# 05-Power.net
KiCad netlist of a schematic drawn in Altium Designer
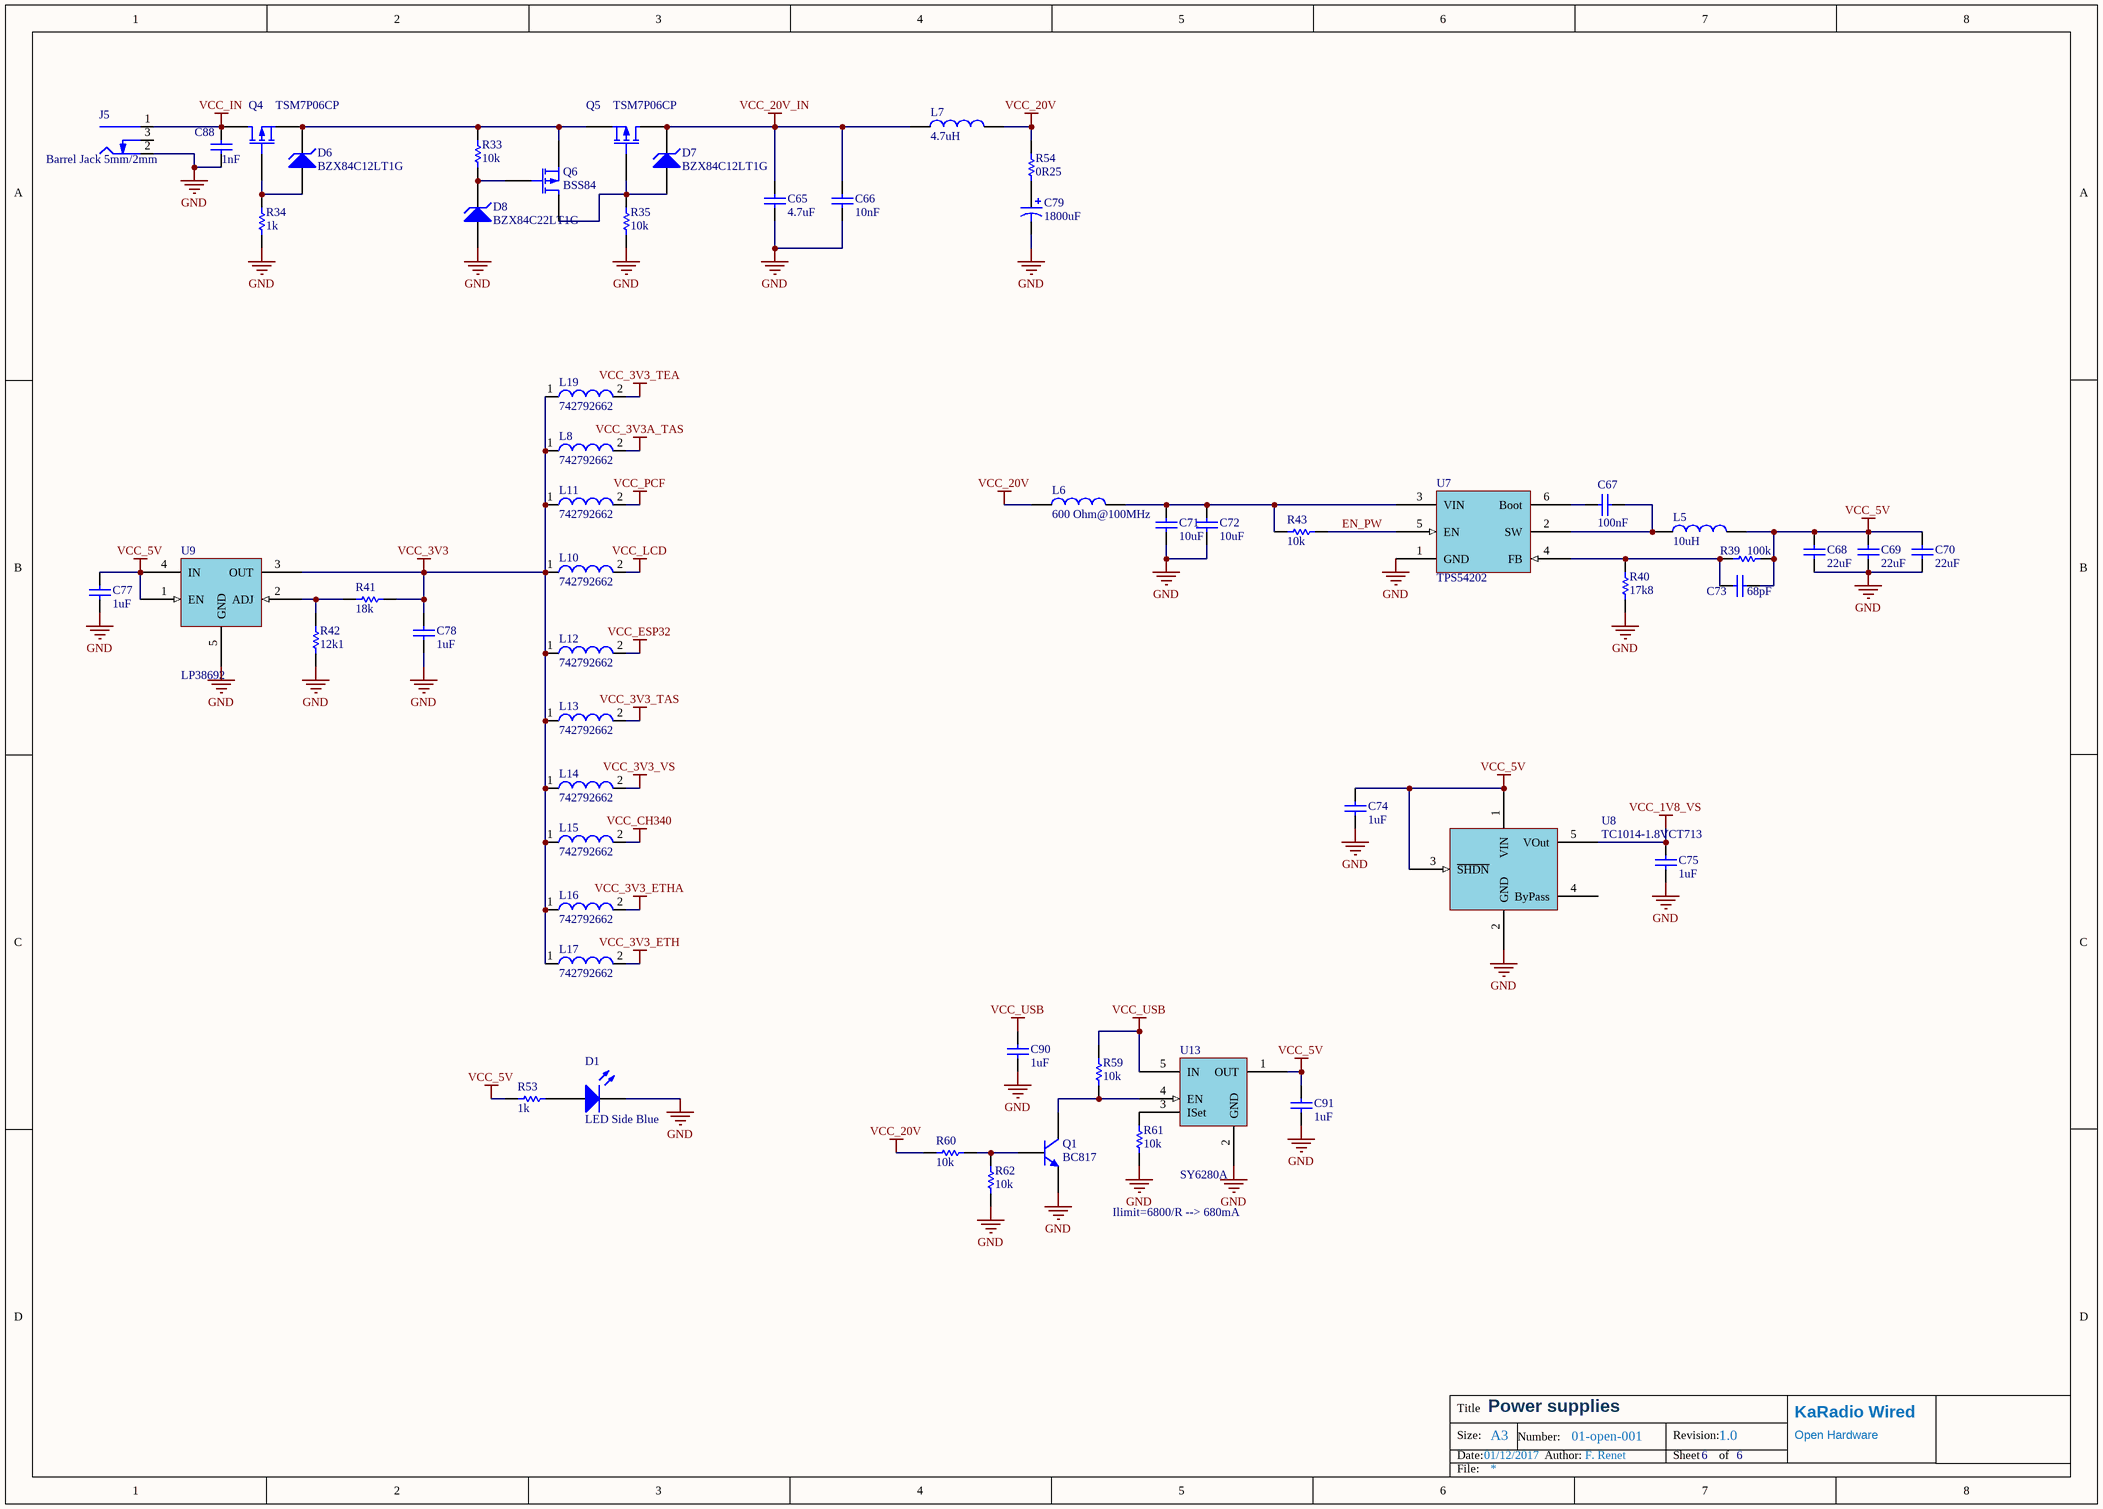
[diagram p0: 05-Power.SchDoc]

(export (version "E")
  (design (tool "Eeschema 10.0.6"))
  (components
    (comp (ref "C65")
      (value "4.7uF")
      (footprint "Aptustech:CAPC3216X16N")
      (description "4.7uF 50V 1206 X5R")
      (fields (field (name "VOLTAGE") "50V") (field (name "TOLERANCE") "10%"))
      (libsource (lib "Cap_1206") (part "4.7uF 50V 1206 X5R"))
    )
    (comp (ref "C66")
      (value "10nF")
      (footprint "Aptustech:CAPC1608X06N")
      (description "10nF 50V 0603 NP0")
      (fields (field (name "VOLTAGE") "50V") (field (name "TOLERANCE") "10%"))
      (libsource (lib "Cap_0603") (part "10nF 50V 0603 NP0"))
    )
    (comp (ref "C67")
      (value "100nF")
      (footprint "Aptustech:CAPC2012X14N")
      (description "100nF 50V 0805 X5R")
      (fields (field (name "VOLTAGE") "50V") (field (name "TOLERANCE") "10%"))
      (libsource (lib "Cap_0805") (part "100nF 50V 0805 X5R_1"))
    )
    (comp (ref "C68")
      (value "22uF")
      (footprint "Aptustech:CAPC2012X14N")
      (description "22uF 10V 0805 X5R")
      (fields (field (name "VOLTAGE") "10V") (field (name "TOLERANCE") "10%"))
      (libsource (lib "Cap_0805") (part "22uF 10V 0805 X5R"))
    )
    (comp (ref "C69")
      (value "22uF")
      (footprint "Aptustech:CAPC2012X14N")
      (description "22uF 10V 0805 X5R")
      (fields (field (name "VOLTAGE") "10V") (field (name "TOLERANCE") "10%"))
      (libsource (lib "Cap_0805") (part "22uF 10V 0805 X5R"))
    )
    (comp (ref "C70")
      (value "22uF")
      (footprint "Aptustech:CAPC2012X14N")
      (description "22uF 10V 0805 X5R")
      (fields (field (name "VOLTAGE") "10V") (field (name "TOLERANCE") "10%"))
      (libsource (lib "Cap_0805") (part "22uF 10V 0805 X5R"))
    )
    (comp (ref "C71")
      (value "10uF")
      (footprint "Aptustech:CAPC3216X16N")
      (description "10uF 50V 1206 X5R")
      (fields (field (name "VOLTAGE") "50V") (field (name "TOLERANCE") "10%"))
      (libsource (lib "Cap_1206") (part "10uF 50V 1206 X5R"))
    )
    (comp (ref "C72")
      (value "10uF")
      (footprint "Aptustech:CAPC3216X16N")
      (description "10uF 50V 1206 X5R")
      (fields (field (name "VOLTAGE") "50V") (field (name "TOLERANCE") "10%"))
      (libsource (lib "Cap_1206") (part "10uF 50V 1206 X5R"))
    )
    (comp (ref "C73")
      (value "68pF")
      (footprint "Aptustech:CAPC1608X06N")
      (description "68pF 50V 0603 NP0")
      (fields (field (name "VOLTAGE") "50V") (field (name "TOLERANCE") "10%"))
      (libsource (lib "Cap_0603") (part "68pF 50V 0603 NP0"))
    )
    (comp (ref "C74")
      (value "1uF")
      (footprint "Aptustech:CAPC1608X06N")
      (description "1uF 16V 0603 X7R")
      (fields (field (name "VOLTAGE") "16V") (field (name "TOLERANCE") "10%"))
      (libsource (lib "Cap_0603") (part "1uF 16V 0603 X7R"))
    )
    (comp (ref "C75")
      (value "1uF")
      (footprint "Aptustech:CAPC1608X06N")
      (description "1uF 16V 0603 X7R")
      (fields (field (name "VOLTAGE") "16V") (field (name "TOLERANCE") "10%"))
      (libsource (lib "Cap_0603") (part "1uF 16V 0603 X7R"))
    )
    (comp (ref "C77")
      (value "1uF")
      (footprint "Aptustech:CAPC1608X06N")
      (description "1uF 16V 0603 X7R")
      (fields (field (name "VOLTAGE") "16V") (field (name "TOLERANCE") "10%"))
      (libsource (lib "Cap_0603") (part "1uF 16V 0603 X7R"))
    )
    (comp (ref "C78")
      (value "1uF")
      (footprint "Aptustech:CAPC1608X06N")
      (description "1uF 16V 0603 X7R")
      (fields (field (name "VOLTAGE") "16V") (field (name "TOLERANCE") "10%"))
      (libsource (lib "Cap_0603") (part "1uF 16V 0603 X7R"))
    )
    (comp (ref "C79")
      (value "1800uF")
      (footprint "Aptustech:Cap_POL_12.5mm_20mm_TH")
      (description "Aluminum Capacitor 1800uF 25V TH 12.5mm 20mm")
      (fields (field (name "VOLTAGE") "25V") (field (name "TOLERANCE") "20%"))
      (libsource (lib "Cap_Aluminum") (part "1800uF 25V 12.5mm 20mm"))
    )
    (comp (ref "C88")
      (value "1nF")
      (footprint "Aptustech:CAPC3216X16N")
      (description "1nF 100V 1206 X7R")
      (fields (field (name "VOLTAGE") "100V") (field (name "TOLERANCE") "10%"))
      (libsource (lib "Cap_1206") (part "1nF 100V 1206 X7R"))
    )
    (comp (ref "C90")
      (value "1uF")
      (footprint "Aptustech:CAPC1608X06N")
      (description "1uF 16V 0603 X7R")
      (fields (field (name "VOLTAGE") "16V") (field (name "TOLERANCE") "10%"))
      (libsource (lib "Cap_0603") (part "1uF 16V 0603 X7R"))
    )
    (comp (ref "C91")
      (value "1uF")
      (footprint "Aptustech:CAPC1608X06N")
      (description "1uF 16V 0603 X7R")
      (fields (field (name "VOLTAGE") "16V") (field (name "TOLERANCE") "10%"))
      (libsource (lib "Cap_0603") (part "1uF 16V 0603 X7R"))
    )
    (comp (ref "D1")
      (value "LED Side Blue")
      (footprint "Aptustech:APA1606")
      (description "Side Emitting LED Blue")
      (fields (field (name "MANUFACTURER") "Kingbtigth") (field (name "PARTNUMBER") "APA1606QBC/D"))
      (libsource (lib "Diodes") (part "LED Side Blue"))
    )
    (comp (ref "D6")
      (value "BZX84C12LT1G")
      (footprint "Aptustech:SOT95P230X110-3N")
      (description "DIODE ZENER 12V 250MW SOT23-3")
      (fields (field (name "MANUFACTURER") "ON Semi"))
      (libsource (lib "Diodes") (part "BZX84C12LT1G"))
    )
    (comp (ref "D7")
      (value "BZX84C12LT1G")
      (footprint "Aptustech:SOT95P230X110-3N")
      (description "DIODE ZENER 12V 250MW SOT23-3")
      (fields (field (name "MANUFACTURER") "ON Semi"))
      (libsource (lib "Diodes") (part "BZX84C12LT1G"))
    )
    (comp (ref "D8")
      (value "BZX84C22LT1G")
      (footprint "Aptustech:SOT95P230X110-3N")
      (description "DIODE ZENER 22V 250MW SOT23-3")
      (fields (field (name "MANUFACTURER") "ON Semi"))
      (libsource (lib "Diodes") (part "BZX84C22LT1G"))
    )
    (comp (ref "J5")
      (value "Barrel Jack 5mm/2mm")
      (footprint "Aptustech:CUI PJ-102AH")
      (description "CONN PWR JACK 2X5.5MM SOLDER")
      (fields (field (name "PARTNUMBER") "PJ-102AH") (field (name "MANUFACTURER") "CUI"))
      (libsource (lib "Connectors") (part "Barrel Connector"))
    )
    (comp (ref "L5")
      (value "10uH")
      (footprint "Aptustech:SRN6045")
      (description "SRN6045-100M 10uH 2.5A 6x6x4,5mm")
      (fields (field (name "PARTNUMBER") "SRN6045-100M") (field (name "MANUFACTURER") "Bourns"))
      (libsource (lib "Inductor") (part "SRN6045-100M"))
    )
    (comp (ref "L6")
      (value "600 Ohm@100MHz")
      (footprint "Aptustech:IND2012X14N")
      (description "0805, 600 Ohm@100MHz, 2.1A")
      (fields (field (name "PARTNUMBER") "74279220601") (field (name "MANUFACTURER") "Wurth"))
      (libsource (lib "Inductor") (part "74279220601"))
    )
    (comp (ref "L7")
      (value "4.7uH")
      (footprint "Aptustech:1255AY")
      (description "1255AY-4R7M=P3 4.7uH 4A")
      (fields (field (name "PARTNUMBER") "1255AY-4R7M=P3") (field (name "MANUFACTURER") "Murata"))
      (libsource (lib "Inductor") (part "1255AY-4R7M=P3"))
    )
    (comp (ref "L8")
      (value "742792662")
      (footprint "PcbLib:CAPC0603(1608)")
      (description "SMD EMI Suppression Ferrite Bead WE-CBF, Z = 1000 Ohm")
      (fields (field (name "MANUFACTURER") "Wurth"))
      (libsource (lib "Altium Content Vault") (part "CMP-0220-00178-1"))
    )
    (comp (ref "L10")
      (value "742792662")
      (footprint "PcbLib:CAPC0603(1608)")
      (description "SMD EMI Suppression Ferrite Bead WE-CBF, Z = 1000 Ohm")
      (fields (field (name "MANUFACTURER") "Wurth"))
      (libsource (lib "Altium Content Vault") (part "CMP-0220-00178-1"))
    )
    (comp (ref "L11")
      (value "742792662")
      (footprint "PcbLib:CAPC0603(1608)")
      (description "SMD EMI Suppression Ferrite Bead WE-CBF, Z = 1000 Ohm")
      (fields (field (name "MANUFACTURER") "Wurth"))
      (libsource (lib "Altium Content Vault") (part "CMP-0220-00178-1"))
    )
    (comp (ref "L12")
      (value "742792662")
      (footprint "PcbLib:CAPC0603(1608)")
      (description "SMD EMI Suppression Ferrite Bead WE-CBF, Z = 1000 Ohm")
      (fields (field (name "MANUFACTURER") "Wurth"))
      (libsource (lib "Altium Content Vault") (part "CMP-0220-00178-1"))
    )
    (comp (ref "L13")
      (value "742792662")
      (footprint "PcbLib:CAPC0603(1608)")
      (description "SMD EMI Suppression Ferrite Bead WE-CBF, Z = 1000 Ohm")
      (fields (field (name "MANUFACTURER") "Wurth"))
      (libsource (lib "Altium Content Vault") (part "CMP-0220-00178-1"))
    )
    (comp (ref "L14")
      (value "742792662")
      (footprint "PcbLib:CAPC0603(1608)")
      (description "SMD EMI Suppression Ferrite Bead WE-CBF, Z = 1000 Ohm")
      (fields (field (name "MANUFACTURER") "Wurth"))
      (libsource (lib "Altium Content Vault") (part "CMP-0220-00178-1"))
    )
    (comp (ref "L15")
      (value "742792662")
      (footprint "PcbLib:CAPC0603(1608)")
      (description "SMD EMI Suppression Ferrite Bead WE-CBF, Z = 1000 Ohm")
      (fields (field (name "MANUFACTURER") "Wurth"))
      (libsource (lib "Altium Content Vault") (part "CMP-0220-00178-1"))
    )
    (comp (ref "L16")
      (value "742792662")
      (footprint "PcbLib:CAPC0603(1608)")
      (description "SMD EMI Suppression Ferrite Bead WE-CBF, Z = 1000 Ohm")
      (fields (field (name "MANUFACTURER") "Wurth"))
      (libsource (lib "Altium Content Vault") (part "CMP-0220-00178-1"))
    )
    (comp (ref "L17")
      (value "742792662")
      (footprint "PcbLib:CAPC0603(1608)")
      (description "SMD EMI Suppression Ferrite Bead WE-CBF, Z = 1000 Ohm")
      (fields (field (name "MANUFACTURER") "Wurth"))
      (libsource (lib "Altium Content Vault") (part "CMP-0220-00178-1"))
    )
    (comp (ref "L19")
      (value "742792662")
      (footprint "CAPC0603(1608)")
      (description "SMD EMI Suppression Ferrite Bead WE-CBF, Z = 1000 Ohm")
      (fields (field (name "MANUFACTURER") "Wurth"))
      (libsource (lib "altium-import") (part "root_0_CMP-0220-00178-1_"))
    )
    (comp (ref "Q1")
      (value "BC817")
      (footprint "Aptustech:SOT95P230X110-3N")
      (description "BC817 NPN  45V SOT23")
      (fields (field (name "PARTNUMBER") "BC817-40,215") (field (name "MANUFACTURER") "Nexperia"))
      (libsource (lib "Transistor_Switch") (part "BC817_SOT23"))
    )
    (comp (ref "Q4")
      (value "TSM7P06CP")
      (footprint "Aptustech:TO252")
      (description "MOSFET P-CHANNEL 60V 7A TO252")
      (fields (field (name "MANUFACTURER") "Taiwan Semiconductor Corp"))
      (libsource (lib "Transistor_Switch") (part "TSM7P06CP"))
    )
    (comp (ref "Q5")
      (value "TSM7P06CP")
      (footprint "Aptustech:TO252")
      (description "MOSFET P-CHANNEL 60V 7A TO252")
      (fields (field (name "MANUFACTURER") "Taiwan Semiconductor Corp"))
      (libsource (lib "Transistor_Switch") (part "TSM7P06CP"))
    )
    (comp (ref "Q6")
      (value "BSS84")
      (footprint "Aptustech:SOT95P230X110-3N")
      (description "MOSFET P-CH 60V 170MA SOT-23")
      (fields (field (name "PARTNUMBER") "BSS84PH6433XTMA1") (field (name "MANUFACTURER") "Infineon"))
      (libsource (lib "Transistor_Switch") (part "BSS84"))
    )
    (comp (ref "R33")
      (value "10k")
      (footprint "Aptustech:RESC1608X06N")
      (description "Resistor 10k 0603 1%")
      (fields (field (name "TOLERANCE") "1%") (field (name "Comment") "10k_0603"))
      (libsource (lib "Res_0603") (part "10k"))
    )
    (comp (ref "R34")
      (value "1k")
      (footprint "Aptustech:RESC1608X06N")
      (description "Resistor 1k 0603 1%")
      (fields (field (name "TOLERANCE") "1%") (field (name "Comment") "1k_0603"))
      (libsource (lib "Res_0603") (part "1k"))
    )
    (comp (ref "R35")
      (value "10k")
      (footprint "Aptustech:RESC1608X06N")
      (description "Resistor 10k 0603 1%")
      (fields (field (name "TOLERANCE") "1%") (field (name "Comment") "10k_0603"))
      (libsource (lib "Res_0603") (part "10k"))
    )
    (comp (ref "R39")
      (value "100k")
      (footprint "Aptustech:RESC1608X06N")
      (description "Resistor 100k 0603 1%")
      (fields (field (name "TOLERANCE") "1%") (field (name "Comment") "100k_0603"))
      (libsource (lib "Res_0603") (part "100k"))
    )
    (comp (ref "R40")
      (value "17k8")
      (footprint "Aptustech:RESC1608X06N")
      (description "Resistor 17k8 0603 1%")
      (fields (field (name "TOLERANCE") "1%") (field (name "Comment") "17k8_0603"))
      (libsource (lib "Res_0603") (part "17k8"))
    )
    (comp (ref "R41")
      (value "18k")
      (footprint "Aptustech:RESC1608X06N")
      (description "Resistor 18k 0603 1%")
      (fields (field (name "TOLERANCE") "1%") (field (name "Comment") "18k_0603"))
      (libsource (lib "Res_0603") (part "18k"))
    )
    (comp (ref "R42")
      (value "12k1")
      (footprint "Aptustech:RESC1608X06N")
      (description "Resistor 12k1 0603 1%")
      (fields (field (name "TOLERANCE") "1%") (field (name "Comment") "12k1_0603"))
      (libsource (lib "Res_0603") (part "12k1"))
    )
    (comp (ref "R43")
      (value "10k")
      (footprint "Aptustech:RESC1608X06N")
      (description "Resistor 10k 0603 1%")
      (fields (field (name "TOLERANCE") "1%") (field (name "Comment") "10k_0603"))
      (libsource (lib "Res_0603") (part "10k"))
    )
    (comp (ref "R53")
      (value "1k")
      (footprint "Aptustech:RESC1608X06N")
      (description "Resistor 1k 0603 1%")
      (fields (field (name "TOLERANCE") "1%") (field (name "Comment") "1k_0603"))
      (libsource (lib "Res_0603") (part "1k"))
    )
    (comp (ref "R54")
      (value "0R25")
      (footprint "Aptustech:RESC3116X07N")
      (description "Resistor 0.25R 1206 1%")
      (fields (field (name "TOLERANCE") "1%") (field (name "Comment") "0R25_1206"))
      (libsource (lib "Res_1206") (part "0R25_1206"))
    )
    (comp (ref "R59")
      (value "10k")
      (footprint "Aptustech:RESC1608X06N")
      (description "Resistor 10k 0603 1%")
      (fields (field (name "TOLERANCE") "1%") (field (name "Comment") "10k_0603"))
      (libsource (lib "Res_0603") (part "10k"))
    )
    (comp (ref "R60")
      (value "10k")
      (footprint "Aptustech:RESC1608X06N")
      (description "Resistor 10k 0603 1%")
      (fields (field (name "TOLERANCE") "1%") (field (name "Comment") "10k_0603"))
      (libsource (lib "Res_0603") (part "10k"))
    )
    (comp (ref "R61")
      (value "10k")
      (footprint "Aptustech:RESC1608X06N")
      (description "Resistor 10k 0603 1%")
      (fields (field (name "TOLERANCE") "1%") (field (name "Comment") "10k_0603"))
      (libsource (lib "Res_0603") (part "10k"))
    )
    (comp (ref "R62")
      (value "10k")
      (footprint "Aptustech:RESC1608X06N")
      (description "Resistor 10k 0603 1%")
      (fields (field (name "TOLERANCE") "1%") (field (name "Comment") "10k_0603"))
      (libsource (lib "Res_0603") (part "10k"))
    )
    (comp (ref "U7")
      (value "TPS54202")
      (footprint "Aptustech:SOT95P245X110-6N")
      (description "4.5V to 28V Input, 2A Output Sync Buck")
      (fields (field (name "PARTNUMBER") "TPS54202DDC") (field (name "MANUFACTURER") "TI"))
      (libsource (lib "LDO_DC-DC") (part "TPS54202"))
    )
    (comp (ref "U8")
      (value "TC1014-1.8VCT713")
      (footprint "Aptustech:SOT95P245X110-5N")
      (description "1.8V LDO 50mA SOT23-5")
      (fields (field (name "MANUFACTURER") "Microchip"))
      (libsource (lib "LDO_DC-DC") (part "TC1014-1.8VCT713"))
    )
    (comp (ref "U9")
      (value "LP38692")
      (footprint "Aptustech:SOT150P700X180-5N")
      (description "REG LIN POS ADJ 1A SOT223-5 LP38692MP-ADJ/NOPB")
      (fields (field (name "PARTNUMBER") "LP38692MP-ADJ/NOPB") (field (name "MANUFACTURER") "TI"))
      (libsource (lib "LDO_DC-DC") (part "LP38692MP-ADJ/NOPB"))
    )
    (comp (ref "U13")
      (value "SY6280A")
      (footprint "Aptustech:SOT95P245X110-5N")
      (description "SOT23-5 USB VCC Switch with current Limit")
      (fields (field (name "MANUFACTURER") "Silergy"))
      (libsource (lib "MISC_IC") (part "SY6280A"))
    )
  )
  (nets
    (net (code "1") (name "/EN_PW") (class "Default")
      (node (ref "R43") (pin "1") (pinfunction "1_1") (pintype "passive"))
      (node (ref "U7") (pin "5") (pinfunction "EN_5") (pintype "input"))
    )
    (net (code "2") (name "GND") (class "Default")
      (node (ref "C65") (pin "1") (pinfunction "1_1") (pintype "passive"))
      (node (ref "C66") (pin "1") (pinfunction "1_1") (pintype "passive"))
      (node (ref "C68") (pin "1") (pinfunction "1_1") (pintype "passive"))
      (node (ref "C69") (pin "1") (pinfunction "1_1") (pintype "passive"))
      (node (ref "C70") (pin "1") (pinfunction "1_1") (pintype "passive"))
      (node (ref "C71") (pin "1") (pinfunction "1_1") (pintype "passive"))
      (node (ref "C72") (pin "1") (pinfunction "1_1") (pintype "passive"))
      (node (ref "C74") (pin "1") (pinfunction "1_1") (pintype "passive"))
      (node (ref "C75") (pin "1") (pinfunction "1_1") (pintype "passive"))
      (node (ref "C77") (pin "1") (pinfunction "1_1") (pintype "passive"))
      (node (ref "C78") (pin "1") (pinfunction "1_1") (pintype "passive"))
      (node (ref "C79") (pin "2") (pinfunction "2_2") (pintype "passive"))
      (node (ref "C88") (pin "1") (pinfunction "1_1") (pintype "passive"))
      (node (ref "C90") (pin "1") (pinfunction "1_1") (pintype "passive"))
      (node (ref "C91") (pin "1") (pinfunction "1_1") (pintype "passive"))
      (node (ref "D1") (pin "1") (pinfunction "K_1") (pintype "passive"))
      (node (ref "D8") (pin "1") (pinfunction "A_1") (pintype "passive"))
      (node (ref "J5") (pin "2") (pinfunction "Outer_2") (pintype "passive"))
      (node (ref "Q1") (pin "2") (pinfunction "E_2") (pintype "passive"))
      (node (ref "R34") (pin "1") (pinfunction "1_1") (pintype "passive"))
      (node (ref "R35") (pin "1") (pinfunction "1_1") (pintype "passive"))
      (node (ref "R40") (pin "1") (pinfunction "1_1") (pintype "passive"))
      (node (ref "R42") (pin "1") (pinfunction "1_1") (pintype "passive"))
      (node (ref "R61") (pin "1") (pinfunction "1_1") (pintype "passive"))
      (node (ref "R62") (pin "2") (pinfunction "2_2") (pintype "passive"))
      (node (ref "U13") (pin "2") (pinfunction "GND_2") (pintype "power_in"))
      (node (ref "U7") (pin "1") (pinfunction "GND_1") (pintype "power_in"))
      (node (ref "U8") (pin "2") (pinfunction "GND_2") (pintype "power_in"))
      (node (ref "U9") (pin "5") (pinfunction "GND_5") (pintype "power_in"))
    )
    (net (code "3") (name "Net-(C79-Pad1)") (class "Default")
      (node (ref "C79") (pin "1") (pinfunction "1_1") (pintype "passive"))
      (node (ref "R54") (pin "1") (pinfunction "1_1") (pintype "passive"))
    )
    (net (code "4") (name "Net-(D1-A)") (class "Default")
      (node (ref "D1") (pin "2") (pinfunction "A_2") (pintype "passive"))
      (node (ref "R53") (pin "1") (pinfunction "1_1") (pintype "passive"))
    )
    (net (code "5") (name "Net-(D6-A)") (class "Default")
      (node (ref "D6") (pin "1") (pinfunction "A_1") (pintype "passive"))
      (node (ref "Q4") (pin "1") (pinfunction "G_1") (pintype "passive"))
      (node (ref "R34") (pin "2") (pinfunction "2_2") (pintype "passive"))
    )
    (net (code "6") (name "Net-(D6-K)") (class "Default")
      (node (ref "D6") (pin "3") (pinfunction "K_3") (pintype "passive"))
      (node (ref "Q4") (pin "3") (pinfunction "S_3") (pintype "passive"))
      (node (ref "Q5") (pin "3") (pinfunction "S_3") (pintype "passive"))
      (node (ref "Q6") (pin "2") (pinfunction "S_2") (pintype "passive"))
      (node (ref "R33") (pin "2") (pinfunction "2_2") (pintype "passive"))
    )
    (net (code "7") (name "Net-(D7-A)") (class "Default")
      (node (ref "D7") (pin "1") (pinfunction "A_1") (pintype "passive"))
      (node (ref "Q5") (pin "1") (pinfunction "G_1") (pintype "passive"))
      (node (ref "Q6") (pin "3") (pinfunction "D_3") (pintype "passive"))
      (node (ref "R35") (pin "2") (pinfunction "2_2") (pintype "passive"))
    )
    (net (code "8") (name "Net-(D8-K)") (class "Default")
      (node (ref "D8") (pin "3") (pinfunction "K_3") (pintype "passive"))
      (node (ref "Q6") (pin "1") (pinfunction "G_1") (pintype "passive"))
      (node (ref "R33") (pin "1") (pinfunction "1_1") (pintype "passive"))
    )
    (net (code "9") (name "Net-(Q1-B)") (class "Default")
      (node (ref "Q1") (pin "1") (pinfunction "B_1") (pintype "passive"))
      (node (ref "R60") (pin "1") (pinfunction "1_1") (pintype "passive"))
      (node (ref "R62") (pin "1") (pinfunction "1_1") (pintype "passive"))
    )
    (net (code "10") (name "Net-(Q1-C)") (class "Default")
      (node (ref "Q1") (pin "3") (pinfunction "C_3") (pintype "passive"))
      (node (ref "R59") (pin "1") (pinfunction "1_1") (pintype "passive"))
      (node (ref "U13") (pin "4") (pinfunction "EN_4") (pintype "input"))
    )
    (net (code "11") (name "Net-(U7-Boot)") (class "Default")
      (node (ref "C67") (pin "1") (pinfunction "1_1") (pintype "passive"))
      (node (ref "U7") (pin "6") (pinfunction "Boot_6") (pintype "passive"))
    )
    (net (code "12") (name "Net-(U7-FB)") (class "Default")
      (node (ref "C73") (pin "1") (pinfunction "1_1") (pintype "passive"))
      (node (ref "R39") (pin "1") (pinfunction "1_1") (pintype "passive"))
      (node (ref "R40") (pin "2") (pinfunction "2_2") (pintype "passive"))
      (node (ref "U7") (pin "4") (pinfunction "FB_4") (pintype "input"))
    )
    (net (code "13") (name "Net-(U7-SW)") (class "Default")
      (node (ref "C67") (pin "2") (pinfunction "2_2") (pintype "passive"))
      (node (ref "L5") (pin "1") (pinfunction "1_1") (pintype "passive"))
      (node (ref "U7") (pin "2") (pinfunction "SW_2") (pintype "power_in"))
    )
    (net (code "14") (name "Net-(U7-VIN)") (class "Default")
      (node (ref "C71") (pin "2") (pinfunction "2_2") (pintype "passive"))
      (node (ref "C72") (pin "2") (pinfunction "2_2") (pintype "passive"))
      (node (ref "L6") (pin "2") (pinfunction "2_2") (pintype "passive"))
      (node (ref "R43") (pin "2") (pinfunction "2_2") (pintype "passive"))
      (node (ref "U7") (pin "3") (pinfunction "VIN_3") (pintype "power_in"))
    )
    (net (code "15") (name "Net-(U9-ADJ)") (class "Default")
      (node (ref "R41") (pin "1") (pinfunction "1_1") (pintype "passive"))
      (node (ref "R42") (pin "2") (pinfunction "2_2") (pintype "passive"))
      (node (ref "U9") (pin "2") (pinfunction "ADJ_2") (pintype "input"))
    )
    (net (code "16") (name "Net-(U13-ISet)") (class "Default")
      (node (ref "R61") (pin "2") (pinfunction "2_2") (pintype "passive"))
      (node (ref "U13") (pin "3") (pinfunction "ISet_3") (pintype "passive"))
    )
    (net (code "17") (name "VCC_1V8_VS") (class "Default")
      (node (ref "C75") (pin "2") (pinfunction "2_2") (pintype "passive"))
      (node (ref "U8") (pin "5") (pinfunction "VOut_5") (pintype "power_in"))
    )
    (net (code "18") (name "VCC_3V3") (class "Default")
      (node (ref "C78") (pin "2") (pinfunction "2_2") (pintype "passive"))
      (node (ref "L10") (pin "1") (pinfunction "1_1") (pintype "passive"))
      (node (ref "L11") (pin "1") (pinfunction "1_1") (pintype "passive"))
      (node (ref "L12") (pin "1") (pinfunction "1_1") (pintype "passive"))
      (node (ref "L13") (pin "1") (pinfunction "1_1") (pintype "passive"))
      (node (ref "L14") (pin "1") (pinfunction "1_1") (pintype "passive"))
      (node (ref "L15") (pin "1") (pinfunction "1_1") (pintype "passive"))
      (node (ref "L16") (pin "1") (pinfunction "1_1") (pintype "passive"))
      (node (ref "L17") (pin "1") (pinfunction "1_1") (pintype "passive"))
      (node (ref "L19") (pin "1") (pinfunction "1_1") (pintype "passive"))
      (node (ref "L8") (pin "1") (pinfunction "1_1") (pintype "passive"))
      (node (ref "R41") (pin "2") (pinfunction "2_2") (pintype "passive"))
      (node (ref "U9") (pin "3") (pinfunction "OUT_3") (pintype "power_in"))
    )
    (net (code "19") (name "VCC_3V3A_TAS") (class "Default")
      (node (ref "L8") (pin "2") (pinfunction "2_2") (pintype "passive"))
    )
    (net (code "20") (name "VCC_3V3_ETH") (class "Default")
      (node (ref "L17") (pin "2") (pinfunction "2_2") (pintype "passive"))
    )
    (net (code "21") (name "VCC_3V3_ETHA") (class "Default")
      (node (ref "L16") (pin "2") (pinfunction "2_2") (pintype "passive"))
    )
    (net (code "22") (name "VCC_3V3_TAS") (class "Default")
      (node (ref "L13") (pin "2") (pinfunction "2_2") (pintype "passive"))
    )
    (net (code "23") (name "VCC_3V3_TEA") (class "Default")
      (node (ref "L19") (pin "2") (pinfunction "2_2") (pintype "passive"))
    )
    (net (code "24") (name "VCC_3V3_VS") (class "Default")
      (node (ref "L14") (pin "2") (pinfunction "2_2") (pintype "passive"))
    )
    (net (code "25") (name "VCC_5V") (class "Default")
      (node (ref "C68") (pin "2") (pinfunction "2_2") (pintype "passive"))
      (node (ref "C69") (pin "2") (pinfunction "2_2") (pintype "passive"))
      (node (ref "C70") (pin "2") (pinfunction "2_2") (pintype "passive"))
      (node (ref "C73") (pin "2") (pinfunction "2_2") (pintype "passive"))
      (node (ref "C74") (pin "2") (pinfunction "2_2") (pintype "passive"))
      (node (ref "C77") (pin "2") (pinfunction "2_2") (pintype "passive"))
      (node (ref "C91") (pin "2") (pinfunction "2_2") (pintype "passive"))
      (node (ref "L5") (pin "2") (pinfunction "2_2") (pintype "passive"))
      (node (ref "R39") (pin "2") (pinfunction "2_2") (pintype "passive"))
      (node (ref "R53") (pin "2") (pinfunction "2_2") (pintype "passive"))
      (node (ref "U13") (pin "1") (pinfunction "OUT_1") (pintype "power_in"))
      (node (ref "U8") (pin "1") (pinfunction "VIN_1") (pintype "power_in"))
      (node (ref "U8") (pin "3") (pinfunction "~{SHDN}_3") (pintype "input"))
      (node (ref "U9") (pin "1") (pinfunction "EN_1") (pintype "input"))
      (node (ref "U9") (pin "4") (pinfunction "IN_4") (pintype "power_in"))
    )
    (net (code "26") (name "VCC_20V") (class "Default")
      (node (ref "L6") (pin "1") (pinfunction "1_1") (pintype "passive"))
      (node (ref "L7") (pin "2") (pinfunction "2_2") (pintype "passive"))
      (node (ref "R54") (pin "2") (pinfunction "2_2") (pintype "passive"))
      (node (ref "R60") (pin "2") (pinfunction "2_2") (pintype "passive"))
    )
    (net (code "27") (name "VCC_20V_IN") (class "Default")
      (node (ref "C65") (pin "2") (pinfunction "2_2") (pintype "passive"))
      (node (ref "C66") (pin "2") (pinfunction "2_2") (pintype "passive"))
      (node (ref "D7") (pin "3") (pinfunction "K_3") (pintype "passive"))
      (node (ref "L7") (pin "1") (pinfunction "1_1") (pintype "passive"))
      (node (ref "Q5") (pin "2") (pinfunction "D_2") (pintype "passive"))
    )
    (net (code "28") (name "VCC_CH340") (class "Default")
      (node (ref "L15") (pin "2") (pinfunction "2_2") (pintype "passive"))
    )
    (net (code "29") (name "VCC_ESP32") (class "Default")
      (node (ref "L12") (pin "2") (pinfunction "2_2") (pintype "passive"))
    )
    (net (code "30") (name "VCC_IN") (class "Default")
      (node (ref "C88") (pin "2") (pinfunction "2_2") (pintype "passive"))
      (node (ref "J5") (pin "1") (pinfunction "Centre_1") (pintype "passive"))
      (node (ref "Q4") (pin "2") (pinfunction "D_2") (pintype "passive"))
    )
    (net (code "31") (name "VCC_LCD") (class "Default")
      (node (ref "L10") (pin "2") (pinfunction "2_2") (pintype "passive"))
    )
    (net (code "32") (name "VCC_PCF") (class "Default")
      (node (ref "L11") (pin "2") (pinfunction "2_2") (pintype "passive"))
    )
    (net (code "33") (name "VCC_USB") (class "Default")
      (node (ref "C90") (pin "2") (pinfunction "2_2") (pintype "passive"))
      (node (ref "R59") (pin "2") (pinfunction "2_2") (pintype "passive"))
      (node (ref "U13") (pin "5") (pinfunction "IN_5") (pintype "power_in"))
    )
    (net (code "34") (name "unconnected-(J5-SW-Pad3)") (class "Default")
      (node (ref "J5") (pin "3") (pinfunction "SW_3") (pintype "passive"))
    )
    (net (code "35") (name "unconnected-(U8-ByPass-Pad4)") (class "Default")
      (node (ref "U8") (pin "4") (pinfunction "ByPass_4") (pintype "passive"))
    )
  )
)
